# can_hub_v1.net
KiCad netlist of a schematic drawn in EAGLE
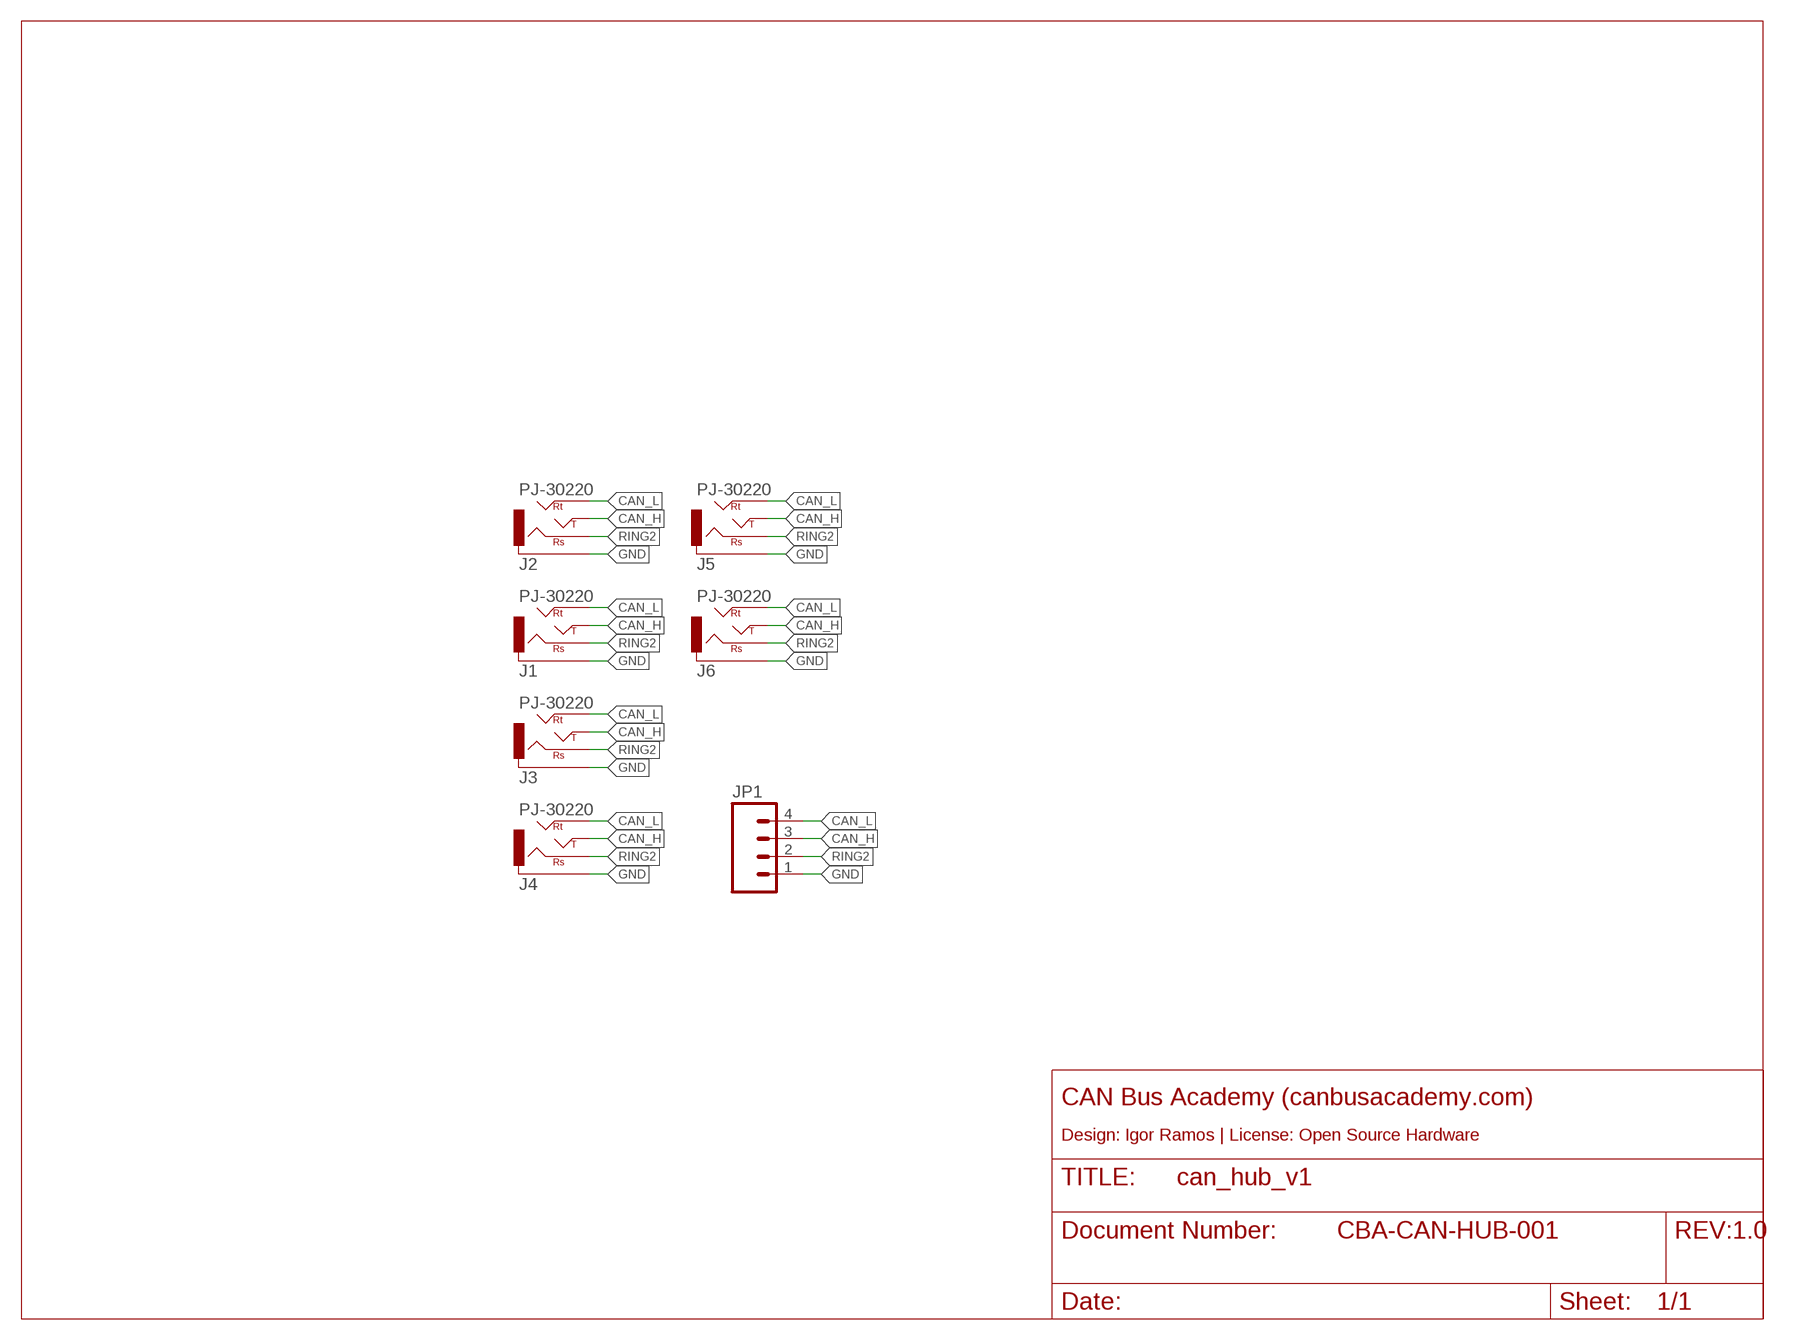
[diagram p0: schematic, sheet 1]

(export (version "E")
  (design (tool "Eeschema 10.0.6"))
  (components
    (comp (ref "J1")
      (value "PJ-30220")
      (footprint "eagle-import:PJ-30220")
      (fields (field (name "PARTNO") "PJ30220"))
      (libsource (lib "eagle-import") (part "AUDIO_JACK_4POSA"))
    )
    (comp (ref "J2")
      (value "PJ-30220")
      (footprint "eagle-import:PJ-30220")
      (fields (field (name "PARTNO") "PJ30220"))
      (libsource (lib "eagle-import") (part "AUDIO_JACK_4POSA"))
    )
    (comp (ref "J3")
      (value "PJ-30220")
      (footprint "eagle-import:PJ-30220")
      (fields (field (name "PARTNO") "PJ30220"))
      (libsource (lib "eagle-import") (part "AUDIO_JACK_4POSA"))
    )
    (comp (ref "J4")
      (value "PJ-30220")
      (footprint "eagle-import:PJ-30220")
      (fields (field (name "PARTNO") "PJ30220"))
      (libsource (lib "eagle-import") (part "AUDIO_JACK_4POSA"))
    )
    (comp (ref "J5")
      (value "PJ-30220")
      (footprint "eagle-import:PJ-30220")
      (fields (field (name "PARTNO") "PJ30220"))
      (libsource (lib "eagle-import") (part "AUDIO_JACK_4POSA"))
    )
    (comp (ref "J6")
      (value "PJ-30220")
      (footprint "eagle-import:PJ-30220")
      (fields (field (name "PARTNO") "PJ30220"))
      (libsource (lib "eagle-import") (part "AUDIO_JACK_4POSA"))
    )
    (comp (ref "JP1")
      (value "M04PTH")
      (footprint "eagle-import:1X04")
      (libsource (lib "eagle-import") (part "M04PTH"))
    )
  )
  (nets
    (net (code "1") (name "CAN_H") (class "Default")
      (node (ref "J1") (pin "P$03") (pinfunction "TIP_P$03") (pintype "bidirectional"))
      (node (ref "J1") (pin "P$03B") (pinfunction "TIP_P$03B") (pintype "bidirectional"))
      (node (ref "J2") (pin "P$03") (pinfunction "TIP_P$03") (pintype "bidirectional"))
      (node (ref "J2") (pin "P$03B") (pinfunction "TIP_P$03B") (pintype "bidirectional"))
      (node (ref "J3") (pin "P$03") (pinfunction "TIP_P$03") (pintype "bidirectional"))
      (node (ref "J3") (pin "P$03B") (pinfunction "TIP_P$03B") (pintype "bidirectional"))
      (node (ref "J4") (pin "P$03") (pinfunction "TIP_P$03") (pintype "bidirectional"))
      (node (ref "J4") (pin "P$03B") (pinfunction "TIP_P$03B") (pintype "bidirectional"))
      (node (ref "J5") (pin "P$03") (pinfunction "TIP_P$03") (pintype "bidirectional"))
      (node (ref "J5") (pin "P$03B") (pinfunction "TIP_P$03B") (pintype "bidirectional"))
      (node (ref "J6") (pin "P$03") (pinfunction "TIP_P$03") (pintype "bidirectional"))
      (node (ref "J6") (pin "P$03B") (pinfunction "TIP_P$03B") (pintype "bidirectional"))
      (node (ref "JP1") (pin "3") (pinfunction "3_3") (pintype "passive"))
    )
    (net (code "2") (name "CAN_L") (class "Default")
      (node (ref "J1") (pin "P$04") (pinfunction "RT_P$04") (pintype "bidirectional"))
      (node (ref "J2") (pin "P$04") (pinfunction "RT_P$04") (pintype "bidirectional"))
      (node (ref "J3") (pin "P$04") (pinfunction "RT_P$04") (pintype "bidirectional"))
      (node (ref "J4") (pin "P$04") (pinfunction "RT_P$04") (pintype "bidirectional"))
      (node (ref "J5") (pin "P$04") (pinfunction "RT_P$04") (pintype "bidirectional"))
      (node (ref "J6") (pin "P$04") (pinfunction "RT_P$04") (pintype "bidirectional"))
      (node (ref "JP1") (pin "4") (pinfunction "4_4") (pintype "passive"))
    )
    (net (code "3") (name "GND") (class "Default")
      (node (ref "J1") (pin "P$01") (pinfunction "SLEEVE_P$01") (pintype "bidirectional"))
      (node (ref "J2") (pin "P$01") (pinfunction "SLEEVE_P$01") (pintype "bidirectional"))
      (node (ref "J3") (pin "P$01") (pinfunction "SLEEVE_P$01") (pintype "bidirectional"))
      (node (ref "J4") (pin "P$01") (pinfunction "SLEEVE_P$01") (pintype "bidirectional"))
      (node (ref "J5") (pin "P$01") (pinfunction "SLEEVE_P$01") (pintype "bidirectional"))
      (node (ref "J6") (pin "P$01") (pinfunction "SLEEVE_P$01") (pintype "bidirectional"))
      (node (ref "JP1") (pin "1") (pinfunction "1_1") (pintype "passive"))
    )
    (net (code "4") (name "RING2") (class "Default")
      (node (ref "J1") (pin "P$02") (pinfunction "RS_P$02") (pintype "bidirectional"))
      (node (ref "J2") (pin "P$02") (pinfunction "RS_P$02") (pintype "bidirectional"))
      (node (ref "J3") (pin "P$02") (pinfunction "RS_P$02") (pintype "bidirectional"))
      (node (ref "J4") (pin "P$02") (pinfunction "RS_P$02") (pintype "bidirectional"))
      (node (ref "J5") (pin "P$02") (pinfunction "RS_P$02") (pintype "bidirectional"))
      (node (ref "J6") (pin "P$02") (pinfunction "RS_P$02") (pintype "bidirectional"))
      (node (ref "JP1") (pin "2") (pinfunction "2_2") (pintype "passive"))
    )
  )
)
